# MT29F2G01_QSPI_NOR_Flash.net
KiCad netlist of a schematic drawn in Altium Designer
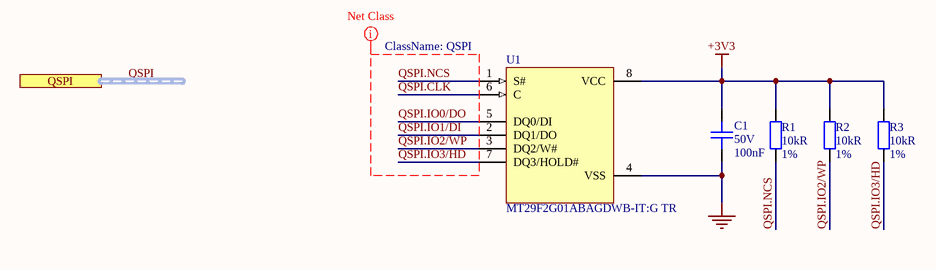
[diagram p0: MT29F2G01_QSPI_NOR_Flash.SchDoc]

(export (version "E")
  (design (tool "Eeschema 10.0.6"))
  (components
    (comp (ref "C1")
      (value "CAP CER 0.1UF 50V X7R 0402")
      (footprint "C0402")
      (description "0.1µF ±10% 50V Ceramic Capacitor X7R 0402 (1005 Metric)")
      (fields
        (field (name "MANUFACTURER PART NUMBER") "CGA2B3X7R1H104K050BB")
        (field (name "MANUFACTURER") "TDK")
        (field (name "VOLTAGE") "50V")
        (field (name "CAPACITANCE") "100nF")
      )
      (libsource (lib "capacitors_smd") (part "CAP CER 0.1UF 50V X7R 0402"))
    )
    (comp (ref "R1")
      (value "RES SMD 10K OHM 1% 1/16W 0402")
      (footprint "R0402")
      (description "10 kOhms ±1% 0.063W, 1/16W Chip Resistor 0402 (1005 Metric) Moisture Resistant Thick Film")
      (fields
        (field (name "MANUFACTURER PART NUMBER") "RC0402FR-0710KP")
        (field (name "MANUFACTURER") "Yageo")
        (field (name "RESISTANCE") "10kR")
        (field (name "TOLERANCE") "1%")
      )
      (libsource (lib "resistors_smd") (part "RES SMD 10K OHM 1% 1/16W 0402"))
    )
    (comp (ref "R2")
      (value "RES SMD 10K OHM 1% 1/16W 0402")
      (footprint "R0402")
      (description "10 kOhms ±1% 0.063W, 1/16W Chip Resistor 0402 (1005 Metric) Moisture Resistant Thick Film")
      (fields
        (field (name "MANUFACTURER PART NUMBER") "RC0402FR-0710KP")
        (field (name "MANUFACTURER") "Yageo")
        (field (name "RESISTANCE") "10kR")
        (field (name "TOLERANCE") "1%")
      )
      (libsource (lib "resistors_smd") (part "RES SMD 10K OHM 1% 1/16W 0402"))
    )
    (comp (ref "R3")
      (value "RES SMD 10K OHM 1% 1/16W 0402")
      (footprint "R0402")
      (description "10 kOhms ±1% 0.063W, 1/16W Chip Resistor 0402 (1005 Metric) Moisture Resistant Thick Film")
      (fields
        (field (name "MANUFACTURER PART NUMBER") "RC0402FR-0710KP")
        (field (name "MANUFACTURER") "Yageo")
        (field (name "RESISTANCE") "10kR")
        (field (name "TOLERANCE") "1%")
      )
      (libsource (lib "resistors_smd") (part "RES SMD 10K OHM 1% 1/16W 0402"))
    )
    (comp (ref "U1")
      (value "MT29F2G01ABAGDWB-IT:G TR")
      (footprint "U-PDFN-8_8X6_P127")
      (description "FLASH - NAND Memory IC 2Gb (2G x 1) SPI 8-U-PDFN (8x6)")
      (fields (field (name "MANUFACTURER") "Micron Technology"))
      (libsource (lib "Control_Board_Model") (part "IC MT29F2G01 FLASH 2G SPI 133MHZ 8UPDFN"))
    )
  )
  (nets
    (net (code "2") (name "+3V3") (class "Default")
      (node (ref "C1") (pin "2") (pinfunction "2_2") (pintype "passive"))
      (node (ref "R1") (pin "1") (pinfunction "1_1") (pintype "passive"))
      (node (ref "R2") (pin "1") (pinfunction "1_1") (pintype "passive"))
      (node (ref "R3") (pin "1") (pinfunction "1_1") (pintype "passive"))
      (node (ref "U1") (pin "8") (pinfunction "VCC_8") (pintype "passive"))
    )
    (net (code "3") (name "/QSPI.CLK") (class "Default")
      (node (ref "U1") (pin "6") (pinfunction "C_6") (pintype "input"))
    )
    (net (code "4") (name "/QSPI.IO0{slash}DO") (class "Default")
      (node (ref "U1") (pin "5") (pinfunction "DQ0/DI_5") (pintype "passive"))
    )
    (net (code "5") (name "/QSPI.IO1{slash}DI") (class "Default")
      (node (ref "U1") (pin "2") (pinfunction "DQ1/DO_2") (pintype "passive"))
    )
    (net (code "6") (name "/QSPI.IO2{slash}WP") (class "Default")
      (node (ref "R2") (pin "2") (pinfunction "2_2") (pintype "passive"))
      (node (ref "U1") (pin "3") (pinfunction "DQ2/W#_3") (pintype "passive"))
    )
    (net (code "7") (name "/QSPI.IO3{slash}HD") (class "Default")
      (node (ref "R3") (pin "2") (pinfunction "2_2") (pintype "passive"))
      (node (ref "U1") (pin "7") (pinfunction "DQ3/HOLD#_7") (pintype "passive"))
    )
    (net (code "8") (name "/QSPI.NCS") (class "Default")
      (node (ref "R1") (pin "2") (pinfunction "2_2") (pintype "passive"))
      (node (ref "U1") (pin "1") (pinfunction "S#_1") (pintype "input"))
    )
    (net (code "10") (name "GND") (class "Default")
      (node (ref "C1") (pin "1") (pinfunction "1_1") (pintype "passive"))
      (node (ref "U1") (pin "4") (pinfunction "VSS_4") (pintype "passive"))
    )
  )
)
